# Potncia.net
KiCad netlist of a schematic drawn in Altium Designer
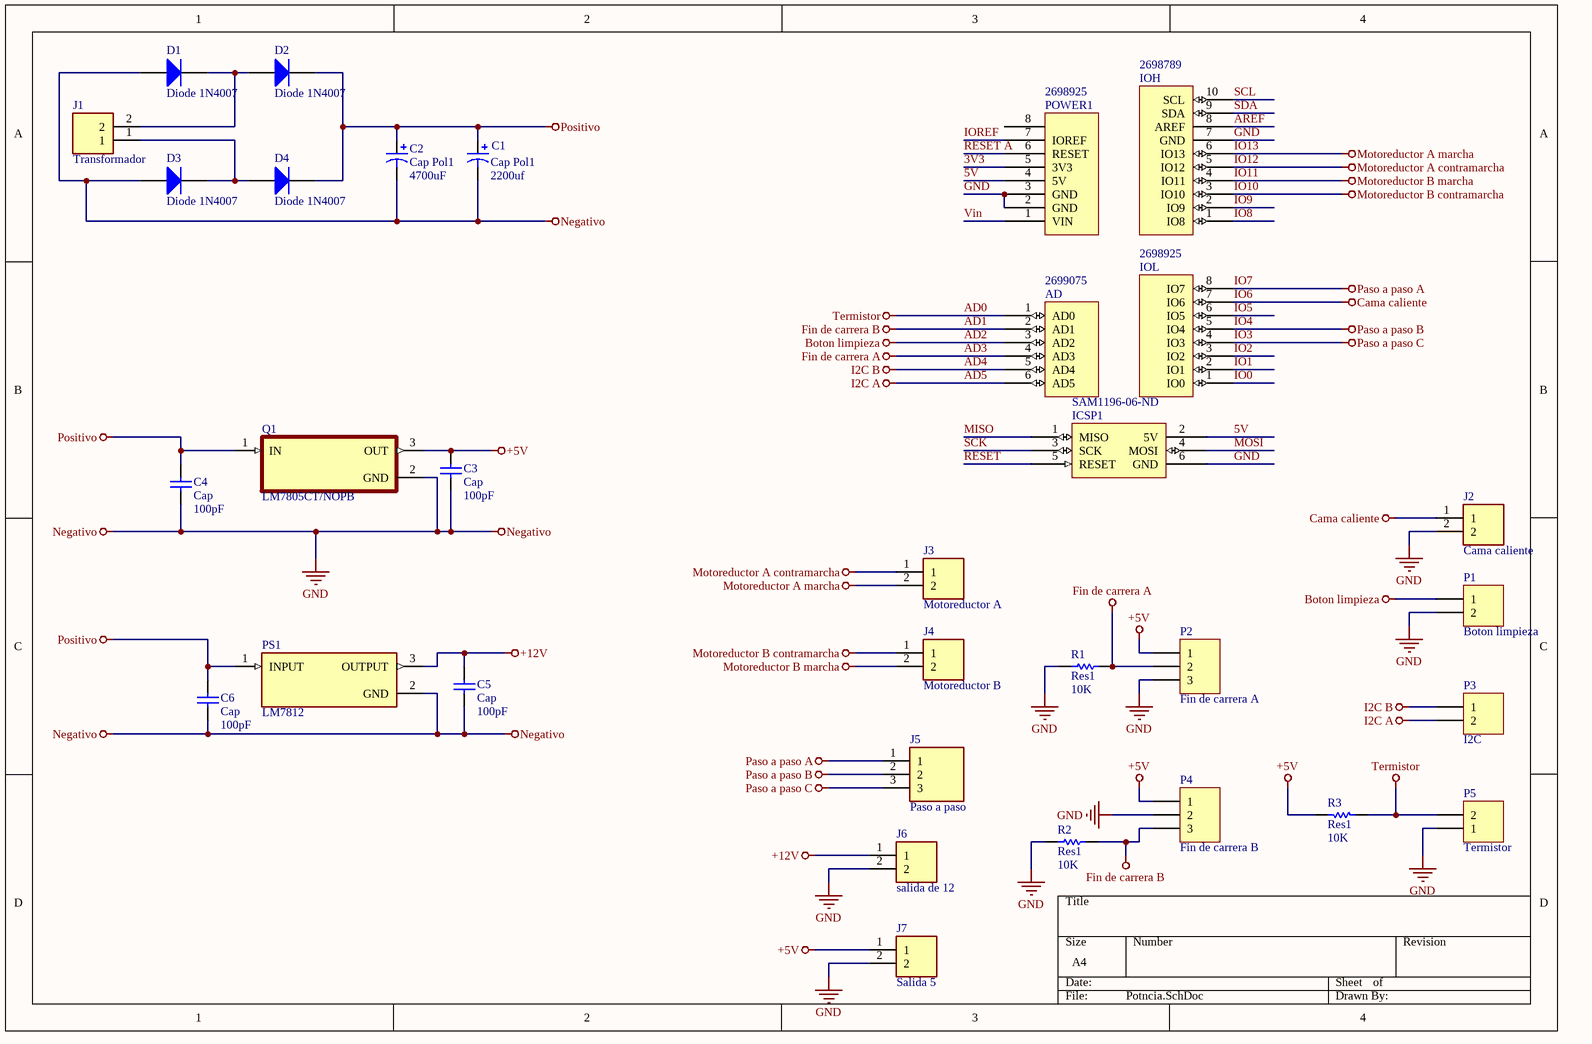
[diagram p0: Potncia.SchDoc]

(export (version "E")
  (design (tool "Eeschema 10.0.6"))
  (components
    (comp (ref "AD")
      (value "AD")
      (footprint "Header:Header 6x1 8.5mm")
      (fields (field (name "SUPPLIER PART NUMBER 4") "2699075"))
      (libsource (lib "Integrated_Library") (part "AD"))
    )
    (comp (ref "C1")
      (value "Cap Pol1")
      (footprint "RB5-10.5")
      (description "Polarized Capacitor (Radial)")
      (fields (field (name "ALTIUM_VALUE") "2200uf") (field (name "PUBLISHER") "Altium Limited"))
      (libsource (lib "Miscellaneous Devices") (part "Cap Pol1"))
    )
    (comp (ref "C2")
      (value "Cap Pol1")
      (footprint "RB5-10.5")
      (description "Polarized Capacitor (Radial)")
      (fields (field (name "ALTIUM_VALUE") "4700uF") (field (name "PUBLISHER") "Altium Limited"))
      (libsource (lib "Miscellaneous Devices") (part "Cap Pol1"))
    )
    (comp (ref "C3")
      (value "Cap")
      (footprint "RAD-0.1")
      (description "Capacitor")
      (fields (field (name "ALTIUM_VALUE") "100pF") (field (name "PUBLISHER") "Altium Limited"))
      (libsource (lib "Miscellaneous Devices") (part "Cap"))
    )
    (comp (ref "C4")
      (value "Cap")
      (footprint "RAD-0.1")
      (description "Capacitor")
      (fields (field (name "ALTIUM_VALUE") "100pF") (field (name "PUBLISHER") "Altium Limited"))
      (libsource (lib "Miscellaneous Devices") (part "Cap"))
    )
    (comp (ref "C5")
      (value "Cap")
      (footprint "RAD-0.1")
      (description "Capacitor")
      (fields (field (name "ALTIUM_VALUE") "100pF") (field (name "PUBLISHER") "Altium Limited"))
      (libsource (lib "Miscellaneous Devices") (part "Cap"))
    )
    (comp (ref "C6")
      (value "Cap")
      (footprint "RAD-0.1")
      (description "Capacitor")
      (fields (field (name "ALTIUM_VALUE") "100pF") (field (name "PUBLISHER") "Altium Limited"))
      (libsource (lib "Miscellaneous Devices") (part "Cap"))
    )
    (comp (ref "D1")
      (value "Diode 1N4007")
      (footprint "DO-35")
      (description "High Conductance Fast Diode")
      (fields (field (name "PUBLISHER") "Altium Limited"))
      (libsource (lib "Miscellaneous Devices") (part "Diode 1N914"))
    )
    (comp (ref "D2")
      (value "Diode 1N4007")
      (footprint "DO-35")
      (description "High Conductance Fast Diode")
      (fields (field (name "PUBLISHER") "Altium Limited"))
      (libsource (lib "Miscellaneous Devices") (part "Diode 1N914"))
    )
    (comp (ref "D3")
      (value "Diode 1N4007")
      (footprint "DO-35")
      (description "High Conductance Fast Diode")
      (fields (field (name "PUBLISHER") "Altium Limited"))
      (libsource (lib "Miscellaneous Devices") (part "Diode 1N914"))
    )
    (comp (ref "D4")
      (value "Diode 1N4007")
      (footprint "DO-35")
      (description "High Conductance Fast Diode")
      (fields (field (name "PUBLISHER") "Altium Limited"))
      (libsource (lib "Miscellaneous Devices") (part "Diode 1N914"))
    )
    (comp (ref "ICSP1")
      (value "ICSP")
      (footprint "ICSP")
      (fields (field (name "SUPPLIER PART NUMBER 5") "SAM1196-06-ND"))
      (libsource (lib "Header") (part "ICSP"))
    )
    (comp (ref "IOH")
      (value "IOH")
      (footprint "Header:Header 10x1 8.5mm")
      (fields (field (name "SUPPLIER PART NUMBER 3") "2698789"))
      (libsource (lib "Integrated_Library") (part "IOH"))
    )
    (comp (ref "IOL")
      (value "IOL")
      (footprint "Header 8x1 8.5mm")
      (fields (field (name "SUPPLIER PART NUMBER 4") "2698925"))
      (libsource (lib "Header") (part "IOL"))
    )
    (comp (ref "J1")
      (value "282841-2")
      (footprint "TE_282841-2")
      (description "Conn Terminal Block 2 POS 5.08mm Solder ST Thru-Hole 17.5A/Contact")
      (fields (field (name "MF") "TE Connectivity") (field (name "COMMENT_1") "Transformador"))
      (libsource (lib "") (part "282841-2_1"))
    )
    (comp (ref "J2")
      (value "282841-2")
      (footprint "TE_282841-2")
      (description "Conn Terminal Block 2 POS 5.08mm Solder ST Thru-Hole 17.5A/Contact")
      (fields (field (name "MF") "TE Connectivity") (field (name "COMMENT_1") "Cama caliente"))
      (libsource (lib "282841-2") (part "282841-2"))
    )
    (comp (ref "J3")
      (value "282841-2")
      (footprint "TE_282841-2")
      (description "Conn Terminal Block 2 POS 5.08mm Solder ST Thru-Hole 17.5A/Contact")
      (fields (field (name "MF") "TE Connectivity") (field (name "COMMENT_1") "Motoreductor A"))
      (libsource (lib "282841-2") (part "282841-2"))
    )
    (comp (ref "J4")
      (value "282841-2")
      (footprint "TE_282841-2")
      (description "Conn Terminal Block 2 POS 5.08mm Solder ST Thru-Hole 17.5A/Contact")
      (fields (field (name "MF") "TE Connectivity") (field (name "COMMENT_1") "Motoreductor B"))
      (libsource (lib "282841-2") (part "282841-2"))
    )
    (comp (ref "J5")
      (value "1776275-3")
      (footprint "TE_1776275-3")
      (description "Wire-To-Board Terminal Block, 3, 250 V, 7 A, 22 Awg, 14 Awg, 2 Mm")
      (fields (field (name "MF") "TE Connectivity") (field (name "COMMENT_1") "Paso a paso"))
      (libsource (lib "1776275-3") (part "1776275-3"))
    )
    (comp (ref "J6")
      (value "282841-2")
      (footprint "TE_282841-2")
      (description "Conn Terminal Block 2 POS 5.08mm Solder ST Thru-Hole 17.5A/Contact")
      (fields (field (name "MF") "TE Connectivity") (field (name "COMMENT_1") "salida de 12"))
      (libsource (lib "282841-2") (part "282841-2"))
    )
    (comp (ref "J7")
      (value "282841-2")
      (footprint "TE_282841-2")
      (description "Conn Terminal Block 2 POS 5.08mm Solder ST Thru-Hole 17.5A/Contact")
      (fields (field (name "MF") "TE Connectivity") (field (name "COMMENT_1") "Salida 5"))
      (libsource (lib "282841-2") (part "282841-2"))
    )
    (comp (ref "P1")
      (value "Boton limpieza")
      (footprint "HDR1X2")
      (description "Header, 2-Pin")
      (fields (field (name "PUBLISHER") "Altium Limited"))
      (libsource (lib "") (part "Header 2_1"))
    )
    (comp (ref "P2")
      (value "Fin de carrera A")
      (footprint "HDR1X3")
      (description "Header, 3-Pin")
      (fields (field (name "PUBLISHER") "Altium Limited"))
      (libsource (lib "Miscellaneous Connectors") (part "Header 3"))
    )
    (comp (ref "P3")
      (value "I2C")
      (footprint "HDR1X2")
      (description "Header, 2-Pin")
      (fields (field (name "PUBLISHER") "Altium Limited"))
      (libsource (lib "") (part "Header 2_1"))
    )
    (comp (ref "P4")
      (value "Fin de carrera B")
      (footprint "HDR1X3")
      (description "Header, 3-Pin")
      (fields (field (name "PUBLISHER") "Altium Limited"))
      (libsource (lib "Miscellaneous Connectors") (part "Header 3"))
    )
    (comp (ref "P5")
      (value "Termistor")
      (footprint "HDR1X2")
      (description "Header, 2-Pin")
      (fields (field (name "PUBLISHER") "Altium Limited"))
      (libsource (lib "Miscellaneous Connectors") (part "Header 2"))
    )
    (comp (ref "POWER1")
      (value "POWER_UNO")
      (footprint "Header 8x1 8.5mm")
      (fields (field (name "SUPPLIER PART NUMBER 4") "2698925"))
      (libsource (lib "Header") (part "POWER_UNO"))
    )
    (comp (ref "PS1")
      (value "LM7812")
      (footprint "VREG_LM7812")
      (description "Linear Voltage Regulator IC 1 Output 1.5A DDPAK/TO-263-3")
      (fields
        (field (name "MF") "Texas Instruments")
        (field (name "BUYPART") "https://www.snapeda.com/parts/LM7812/Texas%20Instruments/view-part/2755251/?ref=eda")
      )
      (libsource (lib "LM7812") (part "LM7812"))
    )
    (comp (ref "Q1")
      (value "LM7805CT/NOPB")
      (footprint "TO254P1054X470X1955-3")
      (description "1.5-A, 30-V, linear voltage regulator 3-TO-220 0 to 125")
      (fields (field (name "MF") "Texas Instruments"))
      (libsource (lib "LM7805CT_NOPB") (part "LM7805CT/NOPB"))
    )
    (comp (ref "R1")
      (value "Res1")
      (footprint "AXIAL-0.3")
      (description "Resistor")
      (fields (field (name "ALTIUM_VALUE") "10K") (field (name "PUBLISHER") "Altium Limited"))
      (libsource (lib "Miscellaneous Devices") (part "Res1"))
    )
    (comp (ref "R2")
      (value "Res1")
      (footprint "AXIAL-0.3")
      (description "Resistor")
      (fields (field (name "ALTIUM_VALUE") "10K") (field (name "PUBLISHER") "Altium Limited"))
      (libsource (lib "Miscellaneous Devices") (part "Res1"))
    )
    (comp (ref "R3")
      (value "Res1")
      (footprint "AXIAL-0.3")
      (description "Resistor")
      (fields (field (name "ALTIUM_VALUE") "10K") (field (name "PUBLISHER") "Altium Limited"))
      (libsource (lib "Miscellaneous Devices") (part "Res1"))
    )
  )
  (nets
    (net (code "1") (name "+5V") (class "Default")
      (node (ref "C3") (pin "2") (pinfunction "2_2") (pintype "passive"))
      (node (ref "J7") (pin "1") (pinfunction "1_1") (pintype "passive"))
      (node (ref "P2") (pin "1") (pinfunction "1_1") (pintype "passive"))
      (node (ref "P4") (pin "1") (pinfunction "1_1") (pintype "passive"))
      (node (ref "Q1") (pin "3") (pinfunction "OUT_3") (pintype "output"))
      (node (ref "R3") (pin "1") (pinfunction "1_1") (pintype "passive"))
    )
    (net (code "2") (name "+12V") (class "Default")
      (node (ref "C5") (pin "2") (pinfunction "2_2") (pintype "passive"))
      (node (ref "J6") (pin "1") (pinfunction "1_1") (pintype "passive"))
      (node (ref "PS1") (pin "3") (pinfunction "OUTPUT_3") (pintype "output"))
    )
    (net (code "3") (name "/3V3") (class "Default")
      (node (ref "POWER1") (pin "5") (pinfunction "3V3_5") (pintype "power_in"))
    )
    (net (code "4") (name "/5V") (class "Default")
      (node (ref "ICSP1") (pin "2") (pinfunction "5V_2") (pintype "power_in"))
      (node (ref "POWER1") (pin "4") (pinfunction "5V_4") (pintype "power_in"))
    )
    (net (code "6") (name "/AREF") (class "Default")
      (node (ref "IOH") (pin "8") (pinfunction "AREF_8") (pintype "passive"))
    )
    (net (code "7") (name "/IO0") (class "Default")
      (node (ref "IOL") (pin "1") (pinfunction "IO0_1") (pintype "bidirectional"))
    )
    (net (code "8") (name "/IO1") (class "Default")
      (node (ref "IOL") (pin "2") (pinfunction "IO1_2") (pintype "bidirectional"))
    )
    (net (code "9") (name "/IO2") (class "Default")
      (node (ref "IOL") (pin "3") (pinfunction "IO2_3") (pintype "bidirectional"))
    )
    (net (code "10") (name "/IO5") (class "Default")
      (node (ref "IOL") (pin "6") (pinfunction "IO5_6") (pintype "bidirectional"))
    )
    (net (code "11") (name "/IO8") (class "Default")
      (node (ref "IOH") (pin "1") (pinfunction "IO8_1") (pintype "bidirectional"))
    )
    (net (code "12") (name "/IO9") (class "Default")
      (node (ref "IOH") (pin "2") (pinfunction "IO9_2") (pintype "bidirectional"))
    )
    (net (code "13") (name "/IOREF") (class "Default")
      (node (ref "POWER1") (pin "7") (pinfunction "IOREF_7") (pintype "power_in"))
    )
    (net (code "14") (name "/MISO") (class "Default")
      (node (ref "ICSP1") (pin "1") (pinfunction "MISO_1") (pintype "bidirectional"))
    )
    (net (code "15") (name "/MOSI") (class "Default")
      (node (ref "ICSP1") (pin "4") (pinfunction "MOSI_4") (pintype "bidirectional"))
    )
    (net (code "16") (name "/RESET") (class "Default")
      (node (ref "ICSP1") (pin "5") (pinfunction "RESET_5") (pintype "input"))
    )
    (net (code "17") (name "/RESET A") (class "Default")
      (node (ref "POWER1") (pin "6") (pinfunction "RESET_6") (pintype "passive"))
    )
    (net (code "18") (name "/SCK") (class "Default")
      (node (ref "ICSP1") (pin "3") (pinfunction "SCK_3") (pintype "bidirectional"))
    )
    (net (code "19") (name "/SCL") (class "Default")
      (node (ref "IOH") (pin "10") (pinfunction "SCL_10") (pintype "bidirectional"))
    )
    (net (code "20") (name "/SDA") (class "Default")
      (node (ref "IOH") (pin "9") (pinfunction "SDA_9") (pintype "bidirectional"))
    )
    (net (code "21") (name "/Vin") (class "Default")
      (node (ref "POWER1") (pin "1") (pinfunction "VIN_1") (pintype "power_in"))
    )
    (net (code "22") (name "Boton limpieza") (class "Default")
      (node (ref "AD") (pin "3") (pinfunction "AD2_3") (pintype "bidirectional"))
      (node (ref "P1") (pin "1") (pinfunction "1_1") (pintype "passive"))
    )
    (net (code "23") (name "Cama caliente") (class "Default")
      (node (ref "IOL") (pin "7") (pinfunction "IO6_7") (pintype "bidirectional"))
      (node (ref "J2") (pin "1") (pinfunction "1_1") (pintype "passive"))
    )
    (net (code "24") (name "Fin de carrera A") (class "Default")
      (node (ref "AD") (pin "4") (pinfunction "AD3_4") (pintype "bidirectional"))
      (node (ref "P2") (pin "2") (pinfunction "2_2") (pintype "passive"))
      (node (ref "R1") (pin "2") (pinfunction "2_2") (pintype "passive"))
    )
    (net (code "25") (name "Fin de carrera B") (class "Default")
      (node (ref "AD") (pin "2") (pinfunction "AD1_2") (pintype "bidirectional"))
      (node (ref "P4") (pin "3") (pinfunction "3_3") (pintype "passive"))
      (node (ref "R2") (pin "2") (pinfunction "2_2") (pintype "passive"))
    )
    (net (code "26") (name "GND") (class "Default")
      (node (ref "C1") (pin "2") (pinfunction "2_2") (pintype "passive"))
      (node (ref "C2") (pin "2") (pinfunction "2_2") (pintype "passive"))
      (node (ref "C3") (pin "1") (pinfunction "1_1") (pintype "passive"))
      (node (ref "C4") (pin "1") (pinfunction "1_1") (pintype "passive"))
      (node (ref "C5") (pin "1") (pinfunction "1_1") (pintype "passive"))
      (node (ref "C6") (pin "1") (pinfunction "1_1") (pintype "passive"))
      (node (ref "D1") (pin "1") (pinfunction "A_1") (pintype "passive"))
      (node (ref "D3") (pin "1") (pinfunction "A_1") (pintype "passive"))
      (node (ref "ICSP1") (pin "6") (pinfunction "GND_6") (pintype "power_in"))
      (node (ref "IOH") (pin "7") (pinfunction "GND_7") (pintype "power_in"))
      (node (ref "J2") (pin "2") (pinfunction "2_2") (pintype "passive"))
      (node (ref "J6") (pin "2") (pinfunction "2_2") (pintype "passive"))
      (node (ref "J7") (pin "2") (pinfunction "2_2") (pintype "passive"))
      (node (ref "P1") (pin "2") (pinfunction "2_2") (pintype "passive"))
      (node (ref "P2") (pin "3") (pinfunction "3_3") (pintype "passive"))
      (node (ref "P4") (pin "2") (pinfunction "2_2") (pintype "passive"))
      (node (ref "P5") (pin "1") (pinfunction "1_1") (pintype "passive"))
      (node (ref "POWER1") (pin "2") (pinfunction "GND_2") (pintype "power_in"))
      (node (ref "POWER1") (pin "3") (pinfunction "GND_3") (pintype "power_in"))
      (node (ref "PS1") (pin "2") (pinfunction "GND_2") (pintype "power_in"))
      (node (ref "Q1") (pin "2") (pinfunction "GND_2") (pintype "power_in"))
      (node (ref "R1") (pin "1") (pinfunction "1_1") (pintype "passive"))
      (node (ref "R2") (pin "1") (pinfunction "1_1") (pintype "passive"))
    )
    (net (code "27") (name "I2C A") (class "Default")
      (node (ref "AD") (pin "6") (pinfunction "AD5_6") (pintype "bidirectional"))
      (node (ref "P3") (pin "2") (pinfunction "2_2") (pintype "passive"))
    )
    (net (code "28") (name "I2C B") (class "Default")
      (node (ref "AD") (pin "5") (pinfunction "AD4_5") (pintype "bidirectional"))
      (node (ref "P3") (pin "1") (pinfunction "1_1") (pintype "passive"))
    )
    (net (code "29") (name "Motoreductor A contramarcha") (class "Default")
      (node (ref "IOH") (pin "5") (pinfunction "IO12_5") (pintype "bidirectional"))
      (node (ref "J3") (pin "1") (pinfunction "1_1") (pintype "passive"))
    )
    (net (code "30") (name "Motoreductor A marcha") (class "Default")
      (node (ref "IOH") (pin "6") (pinfunction "IO13_6") (pintype "bidirectional"))
      (node (ref "J3") (pin "2") (pinfunction "2_2") (pintype "passive"))
    )
    (net (code "31") (name "Motoreductor B contramarcha") (class "Default")
      (node (ref "IOH") (pin "3") (pinfunction "IO10_3") (pintype "bidirectional"))
      (node (ref "J4") (pin "1") (pinfunction "1_1") (pintype "passive"))
    )
    (net (code "32") (name "Motoreductor B marcha") (class "Default")
      (node (ref "IOH") (pin "4") (pinfunction "IO11_4") (pintype "bidirectional"))
      (node (ref "J4") (pin "2") (pinfunction "2_2") (pintype "passive"))
    )
    (net (code "33") (name "Net-(D1-K)") (class "Default")
      (node (ref "D1") (pin "2") (pinfunction "K_2") (pintype "passive"))
      (node (ref "D2") (pin "1") (pinfunction "A_1") (pintype "passive"))
      (node (ref "J1") (pin "2") (pinfunction "2_2") (pintype "passive"))
    )
    (net (code "34") (name "Net-(D3-K)") (class "Default")
      (node (ref "D3") (pin "2") (pinfunction "K_2") (pintype "passive"))
      (node (ref "D4") (pin "1") (pinfunction "A_1") (pintype "passive"))
      (node (ref "J1") (pin "1") (pinfunction "1_1") (pintype "passive"))
    )
    (net (code "35") (name "Paso a paso A") (class "Default")
      (node (ref "IOL") (pin "8") (pinfunction "IO7_8") (pintype "bidirectional"))
      (node (ref "J5") (pin "1") (pinfunction "1_1") (pintype "passive"))
    )
    (net (code "36") (name "Paso a paso B") (class "Default")
      (node (ref "IOL") (pin "5") (pinfunction "IO4_5") (pintype "bidirectional"))
      (node (ref "J5") (pin "2") (pinfunction "2_2") (pintype "passive"))
    )
    (net (code "37") (name "Paso a paso C") (class "Default")
      (node (ref "IOL") (pin "4") (pinfunction "IO3_4") (pintype "bidirectional"))
      (node (ref "J5") (pin "3") (pinfunction "3_3") (pintype "passive"))
    )
    (net (code "38") (name "Positivo") (class "Default")
      (node (ref "C1") (pin "1") (pinfunction "1_1") (pintype "passive"))
      (node (ref "C2") (pin "1") (pinfunction "1_1") (pintype "passive"))
      (node (ref "C4") (pin "2") (pinfunction "2_2") (pintype "passive"))
      (node (ref "C6") (pin "2") (pinfunction "2_2") (pintype "passive"))
      (node (ref "D2") (pin "2") (pinfunction "K_2") (pintype "passive"))
      (node (ref "D4") (pin "2") (pinfunction "K_2") (pintype "passive"))
      (node (ref "PS1") (pin "1") (pinfunction "INPUT_1") (pintype "input"))
      (node (ref "Q1") (pin "1") (pinfunction "IN_1") (pintype "input"))
    )
    (net (code "39") (name "Termistor") (class "Default")
      (node (ref "AD") (pin "1") (pinfunction "AD0_1") (pintype "bidirectional"))
      (node (ref "P5") (pin "2") (pinfunction "2_2") (pintype "passive"))
      (node (ref "R3") (pin "2") (pinfunction "2_2") (pintype "passive"))
    )
    (net (code "40") (name "unconnected-(POWER1-Pad8)") (class "Default")
      (node (ref "POWER1") (pin "8") (pintype "passive"))
    )
  )
)
